# LoRaAdapter.net
KiCad netlist of a schematic drawn in EAGLE
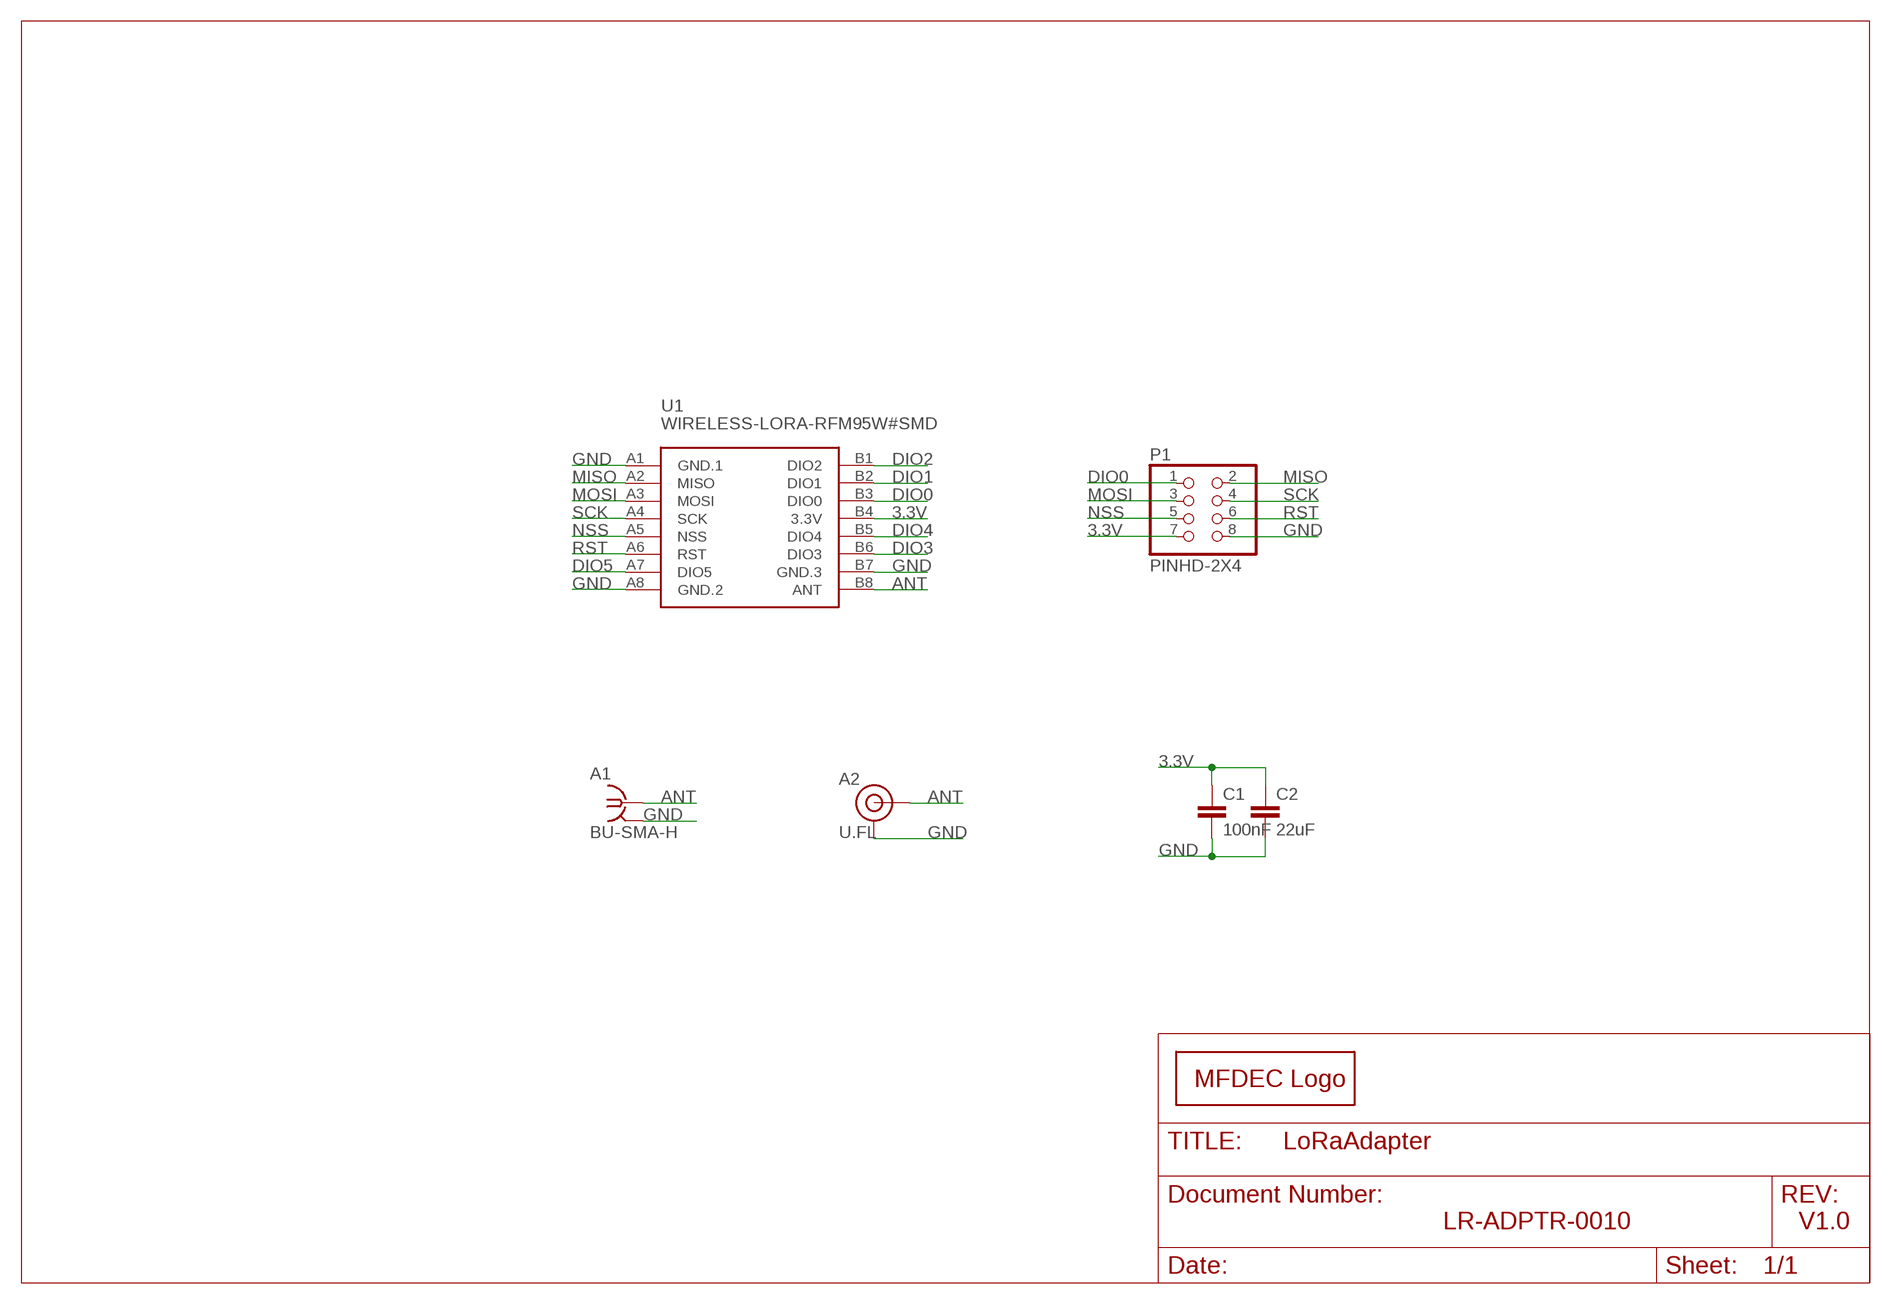
[diagram p0: schematic, sheet 1]

(export (version "E")
  (design (tool "Eeschema 10.0.6"))
  (components
    (comp (ref "A1")
      (value "BU-SMA-H")
      (footprint "eagle-import:BU-SMA-H")
      (libsource (lib "eagle-import") (part "BU-SMA-H"))
    )
    (comp (ref "A2")
      (value "U.FL")
      (footprint "eagle-import:U.FL")
      (libsource (lib "eagle-import") (part "U.FL2PIN"))
    )
    (comp (ref "C1")
      (value "100nF")
      (footprint "eagle-import:C0603")
      (libsource (lib "eagle-import") (part "C-EUC0603"))
    )
    (comp (ref "C2")
      (value "22uF")
      (footprint "eagle-import:C1206")
      (libsource (lib "eagle-import") (part "C-EUC1206"))
    )
    (comp (ref "LOGO1")
      (value "MFDECLOGO_SQ_5MM")
      (footprint "eagle-import:MFDEC_SQ_5MM")
      (libsource (lib "eagle-import") (part "MFDECLOGO_SQ_5MM"))
    )
    (comp (ref "P1")
      (value "PINHD-2X4")
      (footprint "eagle-import:2X04")
      (libsource (lib "eagle-import") (part "PINHD-2X4"))
    )
    (comp (ref "U1")
      (value "WIRELESS-LORA-RFM95W#SMD")
      (footprint "eagle-import:WIRELESS-LORA-RFM95W#SMD")
      (libsource (lib "eagle-import") (part "WIRELESS-LORA-RFM95W#SMD"))
    )
  )
  (nets
    (net (code "1") (name "/3.3V") (class "Default")
      (node (ref "C1") (pin "1") (pinfunction "1_1") (pintype "passive"))
      (node (ref "C2") (pin "1") (pinfunction "1_1") (pintype "passive"))
      (node (ref "P1") (pin "7") (pinfunction "7_7") (pintype "passive"))
      (node (ref "U1") (pin "B4") (pinfunction "3.3V_B4") (pintype "power_in"))
    )
    (net (code "2") (name "/ANT") (class "Default")
      (node (ref "A1") (pin "1") (pinfunction "1_1") (pintype "passive"))
      (node (ref "A2") (pin "FEED") (pinfunction "SIGNAL_FEED") (pintype "bidirectional"))
      (node (ref "U1") (pin "B8") (pinfunction "ANT_B8") (pintype "passive"))
    )
    (net (code "3") (name "/DIO0") (class "Default")
      (node (ref "P1") (pin "1") (pinfunction "1_1") (pintype "passive"))
      (node (ref "U1") (pin "B3") (pinfunction "DIO0_B3") (pintype "bidirectional"))
    )
    (net (code "4") (name "/DIO1") (class "Default")
      (node (ref "U1") (pin "B2") (pinfunction "DIO1_B2") (pintype "bidirectional"))
    )
    (net (code "5") (name "/DIO2") (class "Default")
      (node (ref "U1") (pin "B1") (pinfunction "DIO2_B1") (pintype "bidirectional"))
    )
    (net (code "6") (name "/DIO3") (class "Default")
      (node (ref "U1") (pin "B6") (pinfunction "DIO3_B6") (pintype "bidirectional"))
    )
    (net (code "7") (name "/DIO4") (class "Default")
      (node (ref "U1") (pin "B5") (pinfunction "DIO4_B5") (pintype "bidirectional"))
    )
    (net (code "8") (name "/DIO5") (class "Default")
      (node (ref "U1") (pin "A7") (pinfunction "DIO5_A7") (pintype "bidirectional"))
    )
    (net (code "9") (name "/GND") (class "Default")
      (node (ref "A1") (pin "2") (pinfunction "2_2") (pintype "passive"))
      (node (ref "A1") (pin "3") (pinfunction "2_3") (pintype "passive"))
      (node (ref "A1") (pin "4") (pinfunction "2_4") (pintype "passive"))
      (node (ref "A1") (pin "5") (pinfunction "2_5") (pintype "passive"))
      (node (ref "A2") (pin "1") (pinfunction "GND_1") (pintype "bidirectional"))
      (node (ref "A2") (pin "2") (pinfunction "GND_2") (pintype "bidirectional"))
      (node (ref "C1") (pin "2") (pinfunction "2_2") (pintype "passive"))
      (node (ref "C2") (pin "2") (pinfunction "2_2") (pintype "passive"))
      (node (ref "P1") (pin "8") (pinfunction "8_8") (pintype "passive"))
      (node (ref "U1") (pin "A1") (pinfunction "GND.1_A1") (pintype "power_in"))
      (node (ref "U1") (pin "A8") (pinfunction "GND.2_A8") (pintype "power_in"))
      (node (ref "U1") (pin "B7") (pinfunction "GND.3_B7") (pintype "power_in"))
    )
    (net (code "10") (name "/MISO") (class "Default")
      (node (ref "P1") (pin "2") (pinfunction "2_2") (pintype "passive"))
      (node (ref "U1") (pin "A2") (pinfunction "MISO_A2") (pintype "bidirectional"))
    )
    (net (code "11") (name "/MOSI") (class "Default")
      (node (ref "P1") (pin "3") (pinfunction "3_3") (pintype "passive"))
      (node (ref "U1") (pin "A3") (pinfunction "MOSI_A3") (pintype "bidirectional"))
    )
    (net (code "12") (name "/NSS") (class "Default")
      (node (ref "P1") (pin "5") (pinfunction "5_5") (pintype "passive"))
      (node (ref "U1") (pin "A5") (pinfunction "NSS_A5") (pintype "bidirectional"))
    )
    (net (code "13") (name "/RST") (class "Default")
      (node (ref "P1") (pin "6") (pinfunction "6_6") (pintype "passive"))
      (node (ref "U1") (pin "A6") (pinfunction "RST_A6") (pintype "bidirectional"))
    )
    (net (code "14") (name "/SCK") (class "Default")
      (node (ref "P1") (pin "4") (pinfunction "4_4") (pintype "passive"))
      (node (ref "U1") (pin "A4") (pinfunction "SCK_A4") (pintype "bidirectional"))
    )
  )
)
